# Handle_Interconnect.net
KiCad netlist of a schematic drawn in Altium Designer
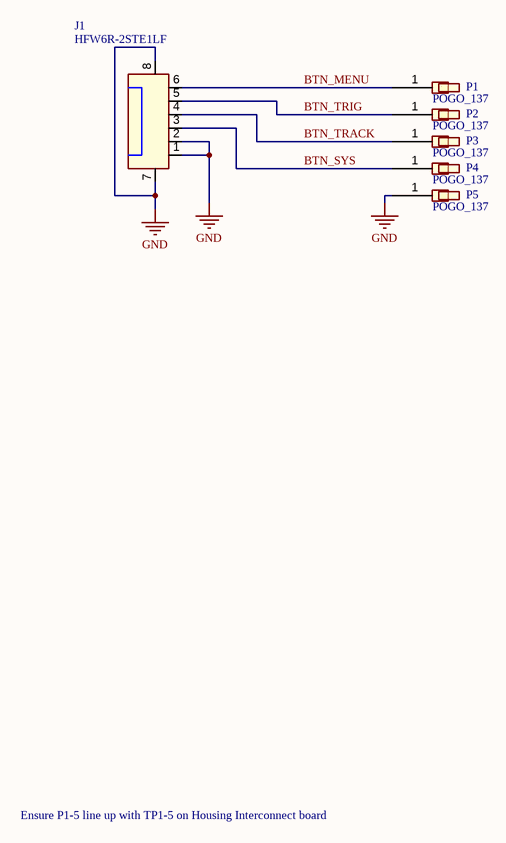
[diagram p0: Handle_Interconnect.SchDoc]

(export (version "E")
  (design (tool "Eeschema 10.0.6"))
  (components
    (comp (ref "J1")
      (value "HFW6R-2STE1LF")
      (footprint "CON_FCI_HFW6R")
      (description "CONN FFC FPC TOP 6POS 1.00MM R/A")
      (fields (field (name "MFG") "Amphenol FCI"))
      (libsource (lib "SynapseLibrary") (part "HEADER 6 TABS"))
    )
    (comp (ref "P1")
      (value "POGO_137")
      (footprint "POGO_MILLMAX_0900-76")
      (description "CONN SPRING LOADED PIN .137 GOLD")
      (fields (field (name "MFG") "MILL-MAX"))
      (libsource (lib "SynapseLibrary") (part "POGO"))
    )
    (comp (ref "P2")
      (value "POGO_137")
      (footprint "POGO_MILLMAX_0900-76")
      (description "CONN SPRING LOADED PIN .137 GOLD")
      (fields (field (name "MFG") "MILL-MAX"))
      (libsource (lib "SynapseLibrary") (part "POGO"))
    )
    (comp (ref "P3")
      (value "POGO_137")
      (footprint "POGO_MILLMAX_0900-76")
      (description "CONN SPRING LOADED PIN .137 GOLD")
      (fields (field (name "MFG") "MILL-MAX"))
      (libsource (lib "SynapseLibrary") (part "POGO"))
    )
    (comp (ref "P4")
      (value "POGO_137")
      (footprint "POGO_MILLMAX_0900-76")
      (description "CONN SPRING LOADED PIN .137 GOLD")
      (fields (field (name "MFG") "MILL-MAX"))
      (libsource (lib "SynapseLibrary") (part "POGO"))
    )
    (comp (ref "P5")
      (value "POGO_137")
      (footprint "POGO_MILLMAX_0900-76")
      (description "CONN SPRING LOADED PIN .137 GOLD")
      (fields (field (name "MFG") "MILL-MAX"))
      (libsource (lib "SynapseLibrary") (part "POGO"))
    )
  )
  (nets
    (net (code "1") (name "/BTN_MENU") (class "Default")
      (node (ref "J1") (pin "6") (pinfunction "6_6") (pintype "passive"))
      (node (ref "P1") (pin "1") (pinfunction "1_1") (pintype "passive"))
    )
    (net (code "2") (name "/BTN_SYS") (class "Default")
      (node (ref "J1") (pin "3") (pinfunction "3_3") (pintype "passive"))
      (node (ref "P4") (pin "1") (pinfunction "1_1") (pintype "passive"))
    )
    (net (code "3") (name "/BTN_TRACK") (class "Default")
      (node (ref "J1") (pin "4") (pinfunction "4_4") (pintype "passive"))
      (node (ref "P3") (pin "1") (pinfunction "1_1") (pintype "passive"))
    )
    (net (code "4") (name "/BTN_TRIG") (class "Default")
      (node (ref "J1") (pin "5") (pinfunction "5_5") (pintype "passive"))
      (node (ref "P2") (pin "1") (pinfunction "1_1") (pintype "passive"))
    )
    (net (code "5") (name "GND") (class "Default")
      (node (ref "J1") (pin "1") (pinfunction "1_1") (pintype "passive"))
      (node (ref "J1") (pin "2") (pinfunction "2_2") (pintype "passive"))
      (node (ref "J1") (pin "7") (pinfunction "7_7") (pintype "passive"))
      (node (ref "J1") (pin "8") (pinfunction "8_8") (pintype "passive"))
      (node (ref "P5") (pin "1") (pinfunction "1_1") (pintype "passive"))
    )
  )
)
